# Arduino_MEGA2560_ref.net
KiCad netlist of a schematic drawn in EAGLE
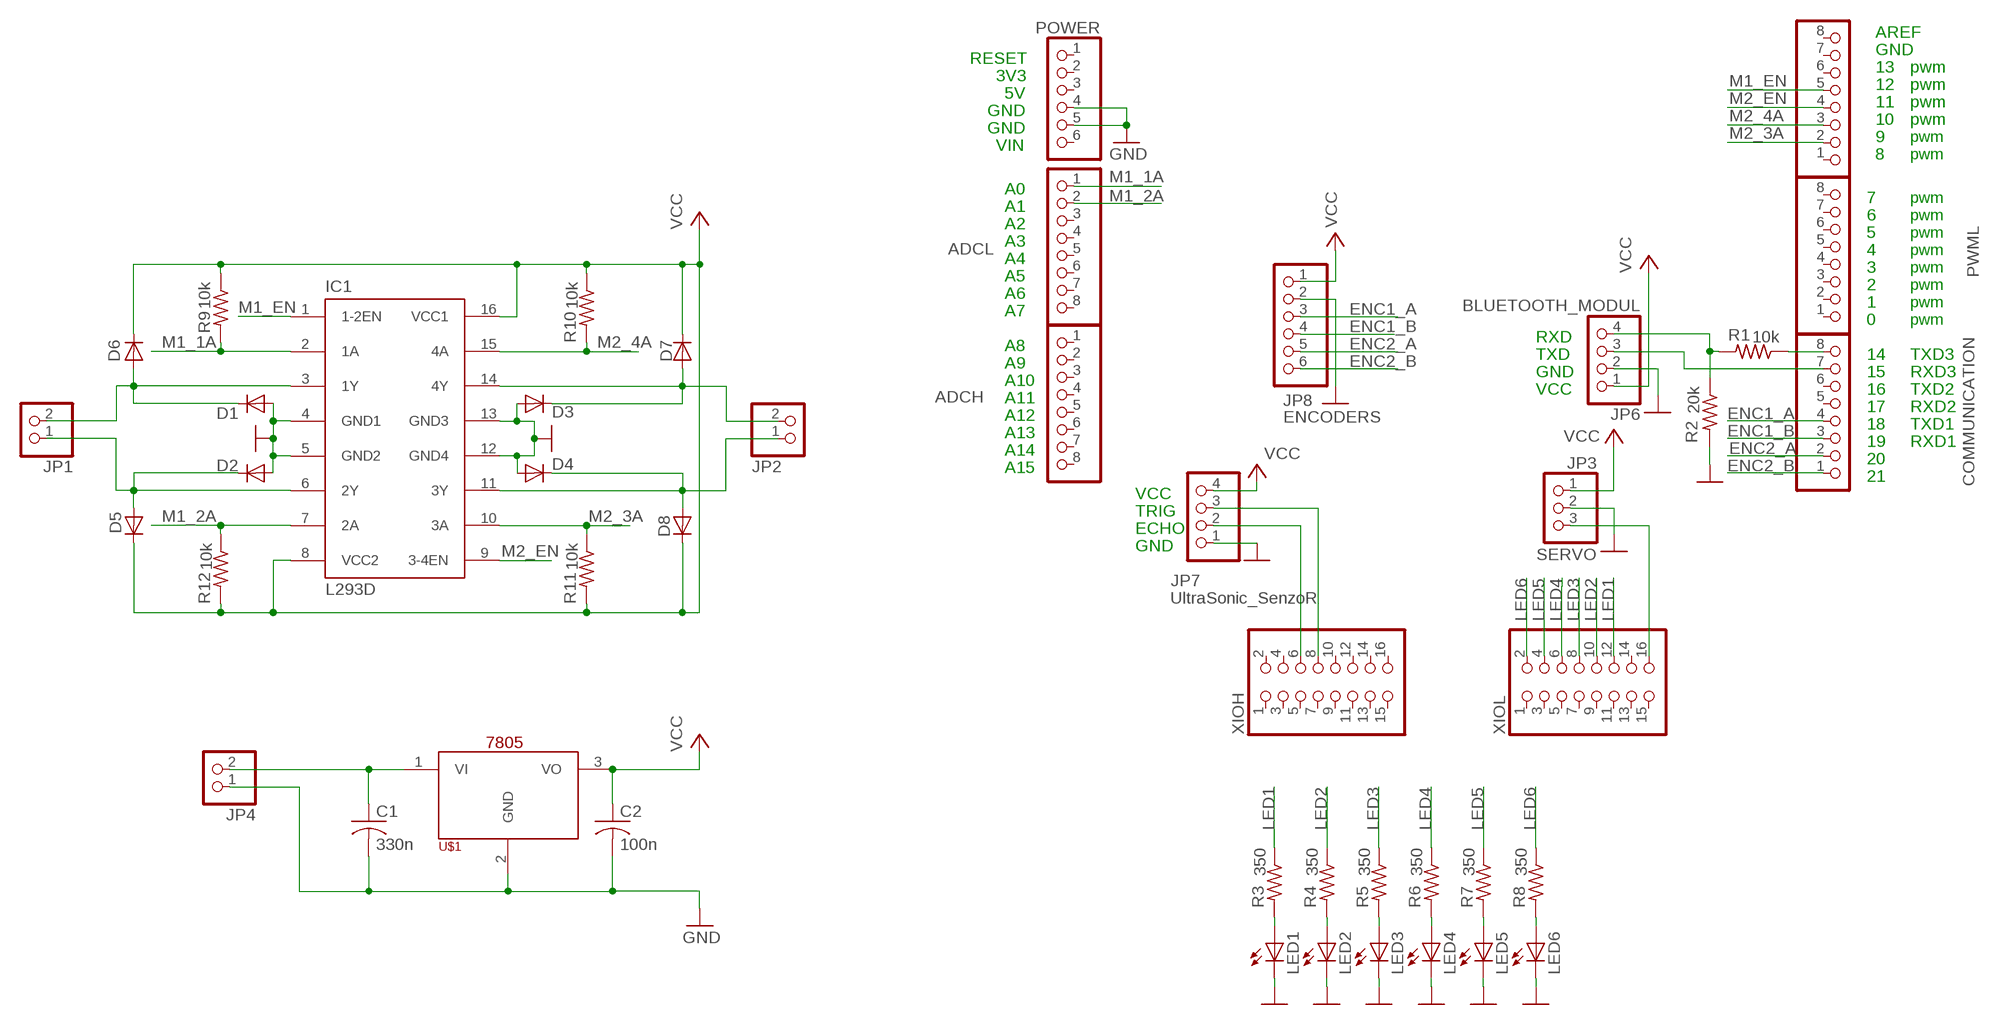
[diagram p0: schematic, sheet 1]

(export (version "E")
  (design (tool "Eeschema 10.0.6"))
  (components
    (comp (ref "ADCH")
      (value "PINHD-1X8")
      (footprint "eagle-import:1X08")
      (libsource (lib "eagle-import") (part "PINHD-1X8"))
    )
    (comp (ref "ADCL")
      (value "PINHD-1X8")
      (footprint "eagle-import:1X08")
      (libsource (lib "eagle-import") (part "PINHD-1X8"))
    )
    (comp (ref "C1")
      (value "330n")
      (footprint "eagle-import:C0805")
      (libsource (lib "eagle-import") (part "C-USC0805"))
    )
    (comp (ref "C2")
      (value "100n")
      (footprint "eagle-import:C0805")
      (libsource (lib "eagle-import") (part "C-USC0805"))
    )
    (comp (ref "COMMUNICATION")
      (value "PINHD-1X8")
      (footprint "eagle-import:1X08")
      (libsource (lib "eagle-import") (part "PINHD-1X8"))
    )
    (comp (ref "D1")
      (value "PMLL4150")
      (footprint "eagle-import:SOD80C")
      (libsource (lib "eagle-import") (part "PMLL4150"))
    )
    (comp (ref "D2")
      (value "PMLL4150")
      (footprint "eagle-import:SOD80C")
      (libsource (lib "eagle-import") (part "PMLL4150"))
    )
    (comp (ref "D3")
      (value "PMLL4150")
      (footprint "eagle-import:SOD80C")
      (libsource (lib "eagle-import") (part "PMLL4150"))
    )
    (comp (ref "D4")
      (value "PMLL4150")
      (footprint "eagle-import:SOD80C")
      (libsource (lib "eagle-import") (part "PMLL4150"))
    )
    (comp (ref "D5")
      (value "PMLL4150")
      (footprint "eagle-import:SOD80C")
      (libsource (lib "eagle-import") (part "PMLL4150"))
    )
    (comp (ref "D6")
      (value "PMLL4150")
      (footprint "eagle-import:SOD80C")
      (libsource (lib "eagle-import") (part "PMLL4150"))
    )
    (comp (ref "D7")
      (value "PMLL4150")
      (footprint "eagle-import:SOD80C")
      (libsource (lib "eagle-import") (part "PMLL4150"))
    )
    (comp (ref "D8")
      (value "PMLL4150")
      (footprint "eagle-import:SOD80C")
      (libsource (lib "eagle-import") (part "PMLL4150"))
    )
    (comp (ref "IC1")
      (value "L293D")
      (footprint "eagle-import:DIL16")
      (libsource (lib "eagle-import") (part "L293D"))
    )
    (comp (ref "JP1")
      (value "PINHD-1X2")
      (footprint "eagle-import:1X02")
      (libsource (lib "eagle-import") (part "PINHD-1X2"))
    )
    (comp (ref "JP2")
      (value "PINHD-1X2")
      (footprint "eagle-import:1X02")
      (libsource (lib "eagle-import") (part "PINHD-1X2"))
    )
    (comp (ref "JP3")
      (value "SERVO")
      (footprint "eagle-import:1X03")
      (libsource (lib "eagle-import") (part "PINHD-1X3"))
    )
    (comp (ref "JP4")
      (value "PINHD-1X2")
      (footprint "eagle-import:1X02")
      (libsource (lib "eagle-import") (part "PINHD-1X2"))
    )
    (comp (ref "JP6")
      (value "BLUETOOTH_MODUL")
      (footprint "eagle-import:1X04")
      (libsource (lib "eagle-import") (part "PINHD-1X4"))
    )
    (comp (ref "JP7")
      (value "UltraSonic_SenzoR")
      (footprint "eagle-import:1X04")
      (libsource (lib "eagle-import") (part "PINHD-1X4"))
    )
    (comp (ref "JP8")
      (value "ENCODERS")
      (footprint "eagle-import:1X06")
      (libsource (lib "eagle-import") (part "PINHD-1X6"))
    )
    (comp (ref "LED1")
      (value "LED")
      (footprint "eagle-import:SMARTLED-TTW")
      (libsource (lib "eagle-import") (part "LED"))
    )
    (comp (ref "LED2")
      (value "LED")
      (footprint "eagle-import:SMARTLED-TTW")
      (libsource (lib "eagle-import") (part "LED"))
    )
    (comp (ref "LED3")
      (value "LED")
      (footprint "eagle-import:SMARTLED-TTW")
      (libsource (lib "eagle-import") (part "LED"))
    )
    (comp (ref "LED4")
      (value "LED")
      (footprint "eagle-import:SMARTLED-TTW")
      (libsource (lib "eagle-import") (part "LED"))
    )
    (comp (ref "LED5")
      (value "LED")
      (footprint "eagle-import:SMARTLED-TTW")
      (libsource (lib "eagle-import") (part "LED"))
    )
    (comp (ref "LED6")
      (value "LED")
      (footprint "eagle-import:SMARTLED-TTW")
      (libsource (lib "eagle-import") (part "LED"))
    )
    (comp (ref "POWER")
      (value "PINHD-1X6")
      (footprint "eagle-import:1X06")
      (libsource (lib "eagle-import") (part "PINHD-1X6"))
    )
    (comp (ref "PWMH")
      (value "PINHD-1X8")
      (footprint "eagle-import:1X08")
      (libsource (lib "eagle-import") (part "PINHD-1X8"))
    )
    (comp (ref "PWML")
      (value "PINHD-1X8")
      (footprint "eagle-import:1X08")
      (libsource (lib "eagle-import") (part "PINHD-1X8"))
    )
    (comp (ref "R1")
      (value "10k")
      (footprint "eagle-import:R0805")
      (libsource (lib "eagle-import") (part "R-US_R0805"))
    )
    (comp (ref "R2")
      (value "20k")
      (footprint "eagle-import:R0805")
      (libsource (lib "eagle-import") (part "R-US_R0805"))
    )
    (comp (ref "R3")
      (value "350")
      (footprint "eagle-import:R0805")
      (libsource (lib "eagle-import") (part "R-US_R0805"))
    )
    (comp (ref "R4")
      (value "350")
      (footprint "eagle-import:R0805")
      (libsource (lib "eagle-import") (part "R-US_R0805"))
    )
    (comp (ref "R5")
      (value "350")
      (footprint "eagle-import:R0805")
      (libsource (lib "eagle-import") (part "R-US_R0805"))
    )
    (comp (ref "R6")
      (value "350")
      (footprint "eagle-import:R0805")
      (libsource (lib "eagle-import") (part "R-US_R0805"))
    )
    (comp (ref "R7")
      (value "350")
      (footprint "eagle-import:R0805")
      (libsource (lib "eagle-import") (part "R-US_R0805"))
    )
    (comp (ref "R8")
      (value "350")
      (footprint "eagle-import:R0805")
      (libsource (lib "eagle-import") (part "R-US_R0805"))
    )
    (comp (ref "R9")
      (value "10k")
      (footprint "eagle-import:R0805")
      (libsource (lib "eagle-import") (part "R-US_R0805"))
    )
    (comp (ref "R10")
      (value "10k")
      (footprint "eagle-import:R0805")
      (libsource (lib "eagle-import") (part "R-US_R0805"))
    )
    (comp (ref "R11")
      (value "10k")
      (footprint "eagle-import:R0805")
      (libsource (lib "eagle-import") (part "R-US_R0805"))
    )
    (comp (ref "R12")
      (value "10k")
      (footprint "eagle-import:R0805")
      (libsource (lib "eagle-import") (part "R-US_R0805"))
    )
    (comp (ref "U$1")
      (value "7805")
      (footprint "eagle-import:TO-220")
      (libsource (lib "eagle-import") (part "7805"))
    )
    (comp (ref "XIOH")
      (value "PINHD-2X8")
      (footprint "eagle-import:2X08")
      (libsource (lib "eagle-import") (part "PINHD-2X8"))
    )
    (comp (ref "XIOL")
      (value "PINHD-2X8")
      (footprint "eagle-import:2X08")
      (libsource (lib "eagle-import") (part "PINHD-2X8"))
    )
  )
  (nets
    (net (code "1") (name "/ENC1_A") (class "Default")
      (node (ref "COMMUNICATION") (pin "4") (pinfunction "4_4") (pintype "passive"))
      (node (ref "JP8") (pin "3") (pinfunction "3_3") (pintype "passive"))
    )
    (net (code "2") (name "/ENC1_B") (class "Default")
      (node (ref "COMMUNICATION") (pin "3") (pinfunction "3_3") (pintype "passive"))
      (node (ref "JP8") (pin "4") (pinfunction "4_4") (pintype "passive"))
    )
    (net (code "3") (name "/ENC2_A") (class "Default")
      (node (ref "COMMUNICATION") (pin "2") (pinfunction "2_2") (pintype "passive"))
      (node (ref "JP8") (pin "5") (pinfunction "5_5") (pintype "passive"))
    )
    (net (code "4") (name "/ENC2_B") (class "Default")
      (node (ref "COMMUNICATION") (pin "1") (pinfunction "1_1") (pintype "passive"))
      (node (ref "JP8") (pin "6") (pinfunction "6_6") (pintype "passive"))
    )
    (net (code "5") (name "/LED1") (class "Default")
      (node (ref "R3") (pin "1") (pinfunction "1_1") (pintype "passive"))
      (node (ref "XIOL") (pin "12") (pinfunction "12_12") (pintype "passive"))
    )
    (net (code "6") (name "/LED2") (class "Default")
      (node (ref "R4") (pin "1") (pinfunction "1_1") (pintype "passive"))
      (node (ref "XIOL") (pin "10") (pinfunction "10_10") (pintype "passive"))
    )
    (net (code "7") (name "/LED3") (class "Default")
      (node (ref "R5") (pin "1") (pinfunction "1_1") (pintype "passive"))
      (node (ref "XIOL") (pin "8") (pinfunction "8_8") (pintype "passive"))
    )
    (net (code "8") (name "/LED4") (class "Default")
      (node (ref "R6") (pin "1") (pinfunction "1_1") (pintype "passive"))
      (node (ref "XIOL") (pin "6") (pinfunction "6_6") (pintype "passive"))
    )
    (net (code "9") (name "/LED5") (class "Default")
      (node (ref "R7") (pin "1") (pinfunction "1_1") (pintype "passive"))
      (node (ref "XIOL") (pin "4") (pinfunction "4_4") (pintype "passive"))
    )
    (net (code "10") (name "/LED6") (class "Default")
      (node (ref "R8") (pin "1") (pinfunction "1_1") (pintype "passive"))
      (node (ref "XIOL") (pin "2") (pinfunction "2_2") (pintype "passive"))
    )
    (net (code "11") (name "/M1_1A") (class "Default")
      (node (ref "ADCL") (pin "1") (pinfunction "1_1") (pintype "passive"))
      (node (ref "IC1") (pin "2") (pinfunction "1A_2") (pintype "input"))
      (node (ref "R9") (pin "2") (pinfunction "2_2") (pintype "passive"))
    )
    (net (code "12") (name "/M1_2A") (class "Default")
      (node (ref "ADCL") (pin "2") (pinfunction "2_2") (pintype "passive"))
      (node (ref "IC1") (pin "7") (pinfunction "2A_7") (pintype "input"))
      (node (ref "R12") (pin "1") (pinfunction "1_1") (pintype "passive"))
    )
    (net (code "13") (name "/M1_EN") (class "Default")
      (node (ref "IC1") (pin "1") (pinfunction "1-2EN_1") (pintype "input"))
      (node (ref "PWMH") (pin "5") (pinfunction "5_5") (pintype "passive"))
    )
    (net (code "14") (name "/M2_3A") (class "Default")
      (node (ref "D4") (pin "C") (pinfunction "C_C") (pintype "passive"))
      (node (ref "D8") (pin "A") (pinfunction "A_A") (pintype "passive"))
      (node (ref "IC1") (pin "11") (pinfunction "3Y_11") (pintype "output"))
      (node (ref "JP2") (pin "1") (pinfunction "1_1") (pintype "passive"))
      (node (ref "PWMH") (pin "2") (pinfunction "2_2") (pintype "passive"))
    )
    (net (code "15") (name "/M2_4A") (class "Default")
      (node (ref "IC1") (pin "15") (pinfunction "4A_15") (pintype "input"))
      (node (ref "PWMH") (pin "3") (pinfunction "3_3") (pintype "passive"))
      (node (ref "R10") (pin "2") (pinfunction "2_2") (pintype "passive"))
    )
    (net (code "16") (name "/M2_EN") (class "Default")
      (node (ref "IC1") (pin "9") (pinfunction "3-4EN_9") (pintype "input"))
      (node (ref "PWMH") (pin "4") (pinfunction "4_4") (pintype "passive"))
    )
    (net (code "17") (name "GND") (class "Default")
      (node (ref "C1") (pin "2") (pinfunction "2_2") (pintype "passive"))
      (node (ref "C2") (pin "2") (pinfunction "2_2") (pintype "passive"))
      (node (ref "D1") (pin "A") (pinfunction "A_A") (pintype "passive"))
      (node (ref "D2") (pin "A") (pinfunction "A_A") (pintype "passive"))
      (node (ref "D3") (pin "A") (pinfunction "A_A") (pintype "passive"))
      (node (ref "D4") (pin "A") (pinfunction "A_A") (pintype "passive"))
      (node (ref "IC1") (pin "12") (pinfunction "GND4_12") (pintype "power_in"))
      (node (ref "IC1") (pin "13") (pinfunction "GND3_13") (pintype "power_in"))
      (node (ref "IC1") (pin "4") (pinfunction "GND1_4") (pintype "power_in"))
      (node (ref "IC1") (pin "5") (pinfunction "GND2_5") (pintype "power_in"))
      (node (ref "JP3") (pin "2") (pinfunction "2_2") (pintype "passive"))
      (node (ref "JP4") (pin "1") (pinfunction "1_1") (pintype "passive"))
      (node (ref "JP6") (pin "2") (pinfunction "2_2") (pintype "passive"))
      (node (ref "JP7") (pin "1") (pinfunction "1_1") (pintype "passive"))
      (node (ref "JP8") (pin "2") (pinfunction "2_2") (pintype "passive"))
      (node (ref "LED1") (pin "C@1") (pinfunction "C_C@1") (pintype "passive"))
      (node (ref "LED2") (pin "C@1") (pinfunction "C_C@1") (pintype "passive"))
      (node (ref "LED3") (pin "C@1") (pinfunction "C_C@1") (pintype "passive"))
      (node (ref "LED4") (pin "C@1") (pinfunction "C_C@1") (pintype "passive"))
      (node (ref "LED5") (pin "C@1") (pinfunction "C_C@1") (pintype "passive"))
      (node (ref "LED6") (pin "C@1") (pinfunction "C_C@1") (pintype "passive"))
      (node (ref "POWER") (pin "4") (pinfunction "4_4") (pintype "passive"))
      (node (ref "POWER") (pin "5") (pinfunction "5_5") (pintype "passive"))
      (node (ref "R2") (pin "2") (pinfunction "2_2") (pintype "passive"))
      (node (ref "U$1") (pin "2") (pinfunction "GND_2") (pintype "bidirectional"))
    )
    (net (code "18") (name "Net-(COMMUNICATION-Pad7)") (class "Default")
      (node (ref "COMMUNICATION") (pin "7") (pinfunction "7_7") (pintype "passive"))
      (node (ref "JP6") (pin "3") (pinfunction "3_3") (pintype "passive"))
    )
    (net (code "19") (name "Net-(COMMUNICATION-Pad8)") (class "Default")
      (node (ref "COMMUNICATION") (pin "8") (pinfunction "8_8") (pintype "passive"))
      (node (ref "R1") (pin "1") (pinfunction "1_1") (pintype "passive"))
    )
    (net (code "20") (name "Net-(IC1-1Y)") (class "Default")
      (node (ref "D1") (pin "C") (pinfunction "C_C") (pintype "passive"))
      (node (ref "D6") (pin "A") (pinfunction "A_A") (pintype "passive"))
      (node (ref "IC1") (pin "3") (pinfunction "1Y_3") (pintype "output"))
      (node (ref "JP1") (pin "2") (pinfunction "2_2") (pintype "passive"))
    )
    (net (code "21") (name "Net-(IC1-2Y)") (class "Default")
      (node (ref "D2") (pin "C") (pinfunction "C_C") (pintype "passive"))
      (node (ref "D5") (pin "A") (pinfunction "A_A") (pintype "passive"))
      (node (ref "IC1") (pin "6") (pinfunction "2Y_6") (pintype "output"))
      (node (ref "JP1") (pin "1") (pinfunction "1_1") (pintype "passive"))
    )
    (net (code "22") (name "Net-(IC1-3A)") (class "Default")
      (node (ref "IC1") (pin "10") (pinfunction "3A_10") (pintype "input"))
      (node (ref "R11") (pin "1") (pinfunction "1_1") (pintype "passive"))
    )
    (net (code "23") (name "Net-(IC1-4Y)") (class "Default")
      (node (ref "D3") (pin "C") (pinfunction "C_C") (pintype "passive"))
      (node (ref "D7") (pin "A") (pinfunction "A_A") (pintype "passive"))
      (node (ref "IC1") (pin "14") (pinfunction "4Y_14") (pintype "output"))
      (node (ref "JP2") (pin "2") (pinfunction "2_2") (pintype "passive"))
    )
    (net (code "24") (name "Net-(JP3-Pad3)") (class "Default")
      (node (ref "JP3") (pin "3") (pinfunction "3_3") (pintype "passive"))
      (node (ref "XIOL") (pin "16") (pinfunction "16_16") (pintype "passive"))
    )
    (net (code "25") (name "Net-(JP6-Pad4)") (class "Default")
      (node (ref "JP6") (pin "4") (pinfunction "4_4") (pintype "passive"))
      (node (ref "R1") (pin "2") (pinfunction "2_2") (pintype "passive"))
      (node (ref "R2") (pin "1") (pinfunction "1_1") (pintype "passive"))
    )
    (net (code "26") (name "Net-(JP7-Pad2)") (class "Default")
      (node (ref "JP7") (pin "2") (pinfunction "2_2") (pintype "passive"))
      (node (ref "XIOH") (pin "6") (pinfunction "6_6") (pintype "passive"))
    )
    (net (code "27") (name "Net-(JP7-Pad3)") (class "Default")
      (node (ref "JP7") (pin "3") (pinfunction "3_3") (pintype "passive"))
      (node (ref "XIOH") (pin "8") (pinfunction "8_8") (pintype "passive"))
    )
    (net (code "28") (name "Net-(LED1-A)") (class "Default")
      (node (ref "LED1") (pin "A@1") (pinfunction "A_A@1") (pintype "passive"))
      (node (ref "R3") (pin "2") (pinfunction "2_2") (pintype "passive"))
    )
    (net (code "29") (name "Net-(LED2-A)") (class "Default")
      (node (ref "LED2") (pin "A@1") (pinfunction "A_A@1") (pintype "passive"))
      (node (ref "R4") (pin "2") (pinfunction "2_2") (pintype "passive"))
    )
    (net (code "30") (name "Net-(LED3-A)") (class "Default")
      (node (ref "LED3") (pin "A@1") (pinfunction "A_A@1") (pintype "passive"))
      (node (ref "R5") (pin "2") (pinfunction "2_2") (pintype "passive"))
    )
    (net (code "31") (name "Net-(LED4-A)") (class "Default")
      (node (ref "LED4") (pin "A@1") (pinfunction "A_A@1") (pintype "passive"))
      (node (ref "R6") (pin "2") (pinfunction "2_2") (pintype "passive"))
    )
    (net (code "32") (name "Net-(LED5-A)") (class "Default")
      (node (ref "LED5") (pin "A@1") (pinfunction "A_A@1") (pintype "passive"))
      (node (ref "R7") (pin "2") (pinfunction "2_2") (pintype "passive"))
    )
    (net (code "33") (name "Net-(LED6-A)") (class "Default")
      (node (ref "LED6") (pin "A@1") (pinfunction "A_A@1") (pintype "passive"))
      (node (ref "R8") (pin "2") (pinfunction "2_2") (pintype "passive"))
    )
    (net (code "34") (name "Net-(U$1-VI)") (class "Default")
      (node (ref "C1") (pin "1") (pinfunction "1_1") (pintype "passive"))
      (node (ref "JP4") (pin "2") (pinfunction "2_2") (pintype "passive"))
      (node (ref "U$1") (pin "1") (pinfunction "VI_1") (pintype "bidirectional"))
    )
    (net (code "35") (name "VCC") (class "Default")
      (node (ref "C2") (pin "1") (pinfunction "1_1") (pintype "passive"))
      (node (ref "D5") (pin "C") (pinfunction "C_C") (pintype "passive"))
      (node (ref "D6") (pin "C") (pinfunction "C_C") (pintype "passive"))
      (node (ref "D7") (pin "C") (pinfunction "C_C") (pintype "passive"))
      (node (ref "D8") (pin "C") (pinfunction "C_C") (pintype "passive"))
      (node (ref "IC1") (pin "16") (pinfunction "VCC1_16") (pintype "power_in"))
      (node (ref "IC1") (pin "8") (pinfunction "VCC2_8") (pintype "power_in"))
      (node (ref "JP3") (pin "1") (pinfunction "1_1") (pintype "passive"))
      (node (ref "JP6") (pin "1") (pinfunction "1_1") (pintype "passive"))
      (node (ref "JP7") (pin "4") (pinfunction "4_4") (pintype "passive"))
      (node (ref "JP8") (pin "1") (pinfunction "1_1") (pintype "passive"))
      (node (ref "R10") (pin "1") (pinfunction "1_1") (pintype "passive"))
      (node (ref "R11") (pin "2") (pinfunction "2_2") (pintype "passive"))
      (node (ref "R12") (pin "2") (pinfunction "2_2") (pintype "passive"))
      (node (ref "R9") (pin "1") (pinfunction "1_1") (pintype "passive"))
      (node (ref "U$1") (pin "3") (pinfunction "VO_3") (pintype "bidirectional"))
    )
    (net (code "36") (name "unconnected-(ADCH-Pad1)") (class "Default")
      (node (ref "ADCH") (pin "1") (pinfunction "1_1") (pintype "passive"))
    )
    (net (code "37") (name "unconnected-(ADCH-Pad2)") (class "Default")
      (node (ref "ADCH") (pin "2") (pinfunction "2_2") (pintype "passive"))
    )
    (net (code "38") (name "unconnected-(ADCH-Pad3)") (class "Default")
      (node (ref "ADCH") (pin "3") (pinfunction "3_3") (pintype "passive"))
    )
    (net (code "39") (name "unconnected-(ADCH-Pad4)") (class "Default")
      (node (ref "ADCH") (pin "4") (pinfunction "4_4") (pintype "passive"))
    )
    (net (code "40") (name "unconnected-(ADCH-Pad5)") (class "Default")
      (node (ref "ADCH") (pin "5") (pinfunction "5_5") (pintype "passive"))
    )
    (net (code "41") (name "unconnected-(ADCH-Pad6)") (class "Default")
      (node (ref "ADCH") (pin "6") (pinfunction "6_6") (pintype "passive"))
    )
    (net (code "42") (name "unconnected-(ADCH-Pad7)") (class "Default")
      (node (ref "ADCH") (pin "7") (pinfunction "7_7") (pintype "passive"))
    )
    (net (code "43") (name "unconnected-(ADCH-Pad8)") (class "Default")
      (node (ref "ADCH") (pin "8") (pinfunction "8_8") (pintype "passive"))
    )
    (net (code "44") (name "unconnected-(ADCL-Pad3)") (class "Default")
      (node (ref "ADCL") (pin "3") (pinfunction "3_3") (pintype "passive"))
    )
    (net (code "45") (name "unconnected-(ADCL-Pad4)") (class "Default")
      (node (ref "ADCL") (pin "4") (pinfunction "4_4") (pintype "passive"))
    )
    (net (code "46") (name "unconnected-(ADCL-Pad5)") (class "Default")
      (node (ref "ADCL") (pin "5") (pinfunction "5_5") (pintype "passive"))
    )
    (net (code "47") (name "unconnected-(ADCL-Pad6)") (class "Default")
      (node (ref "ADCL") (pin "6") (pinfunction "6_6") (pintype "passive"))
    )
    (net (code "48") (name "unconnected-(ADCL-Pad7)") (class "Default")
      (node (ref "ADCL") (pin "7") (pinfunction "7_7") (pintype "passive"))
    )
    (net (code "49") (name "unconnected-(ADCL-Pad8)") (class "Default")
      (node (ref "ADCL") (pin "8") (pinfunction "8_8") (pintype "passive"))
    )
    (net (code "50") (name "unconnected-(COMMUNICATION-Pad5)") (class "Default")
      (node (ref "COMMUNICATION") (pin "5") (pinfunction "5_5") (pintype "passive"))
    )
    (net (code "51") (name "unconnected-(COMMUNICATION-Pad6)") (class "Default")
      (node (ref "COMMUNICATION") (pin "6") (pinfunction "6_6") (pintype "passive"))
    )
    (net (code "52") (name "unconnected-(POWER-Pad1)") (class "Default")
      (node (ref "POWER") (pin "1") (pinfunction "1_1") (pintype "passive"))
    )
    (net (code "53") (name "unconnected-(POWER-Pad2)") (class "Default")
      (node (ref "POWER") (pin "2") (pinfunction "2_2") (pintype "passive"))
    )
    (net (code "54") (name "unconnected-(POWER-Pad3)") (class "Default")
      (node (ref "POWER") (pin "3") (pinfunction "3_3") (pintype "passive"))
    )
    (net (code "55") (name "unconnected-(POWER-Pad6)") (class "Default")
      (node (ref "POWER") (pin "6") (pinfunction "6_6") (pintype "passive"))
    )
    (net (code "56") (name "unconnected-(PWMH-Pad1)") (class "Default")
      (node (ref "PWMH") (pin "1") (pinfunction "1_1") (pintype "passive"))
    )
    (net (code "57") (name "unconnected-(PWMH-Pad6)") (class "Default")
      (node (ref "PWMH") (pin "6") (pinfunction "6_6") (pintype "passive"))
    )
    (net (code "58") (name "unconnected-(PWMH-Pad7)") (class "Default")
      (node (ref "PWMH") (pin "7") (pinfunction "7_7") (pintype "passive"))
    )
    (net (code "59") (name "unconnected-(PWMH-Pad8)") (class "Default")
      (node (ref "PWMH") (pin "8") (pinfunction "8_8") (pintype "passive"))
    )
    (net (code "60") (name "unconnected-(PWML-Pad1)") (class "Default")
      (node (ref "PWML") (pin "1") (pinfunction "1_1") (pintype "passive"))
    )
    (net (code "61") (name "unconnected-(PWML-Pad2)") (class "Default")
      (node (ref "PWML") (pin "2") (pinfunction "2_2") (pintype "passive"))
    )
    (net (code "62") (name "unconnected-(PWML-Pad3)") (class "Default")
      (node (ref "PWML") (pin "3") (pinfunction "3_3") (pintype "passive"))
    )
    (net (code "63") (name "unconnected-(PWML-Pad4)") (class "Default")
      (node (ref "PWML") (pin "4") (pinfunction "4_4") (pintype "passive"))
    )
    (net (code "64") (name "unconnected-(PWML-Pad5)") (class "Default")
      (node (ref "PWML") (pin "5") (pinfunction "5_5") (pintype "passive"))
    )
    (net (code "65") (name "unconnected-(PWML-Pad6)") (class "Default")
      (node (ref "PWML") (pin "6") (pinfunction "6_6") (pintype "passive"))
    )
    (net (code "66") (name "unconnected-(PWML-Pad7)") (class "Default")
      (node (ref "PWML") (pin "7") (pinfunction "7_7") (pintype "passive"))
    )
    (net (code "67") (name "unconnected-(PWML-Pad8)") (class "Default")
      (node (ref "PWML") (pin "8") (pinfunction "8_8") (pintype "passive"))
    )
    (net (code "68") (name "unconnected-(XIOH-Pad1)") (class "Default")
      (node (ref "XIOH") (pin "1") (pinfunction "1_1") (pintype "passive"))
    )
    (net (code "69") (name "unconnected-(XIOH-Pad2)") (class "Default")
      (node (ref "XIOH") (pin "2") (pinfunction "2_2") (pintype "passive"))
    )
    (net (code "70") (name "unconnected-(XIOH-Pad3)") (class "Default")
      (node (ref "XIOH") (pin "3") (pinfunction "3_3") (pintype "passive"))
    )
    (net (code "71") (name "unconnected-(XIOH-Pad4)") (class "Default")
      (node (ref "XIOH") (pin "4") (pinfunction "4_4") (pintype "passive"))
    )
    (net (code "72") (name "unconnected-(XIOH-Pad5)") (class "Default")
      (node (ref "XIOH") (pin "5") (pinfunction "5_5") (pintype "passive"))
    )
    (net (code "73") (name "unconnected-(XIOH-Pad7)") (class "Default")
      (node (ref "XIOH") (pin "7") (pinfunction "7_7") (pintype "passive"))
    )
    (net (code "74") (name "unconnected-(XIOH-Pad9)") (class "Default")
      (node (ref "XIOH") (pin "9") (pinfunction "9_9") (pintype "passive"))
    )
    (net (code "75") (name "unconnected-(XIOH-Pad10)") (class "Default")
      (node (ref "XIOH") (pin "10") (pinfunction "10_10") (pintype "passive"))
    )
    (net (code "76") (name "unconnected-(XIOH-Pad11)") (class "Default")
      (node (ref "XIOH") (pin "11") (pinfunction "11_11") (pintype "passive"))
    )
    (net (code "77") (name "unconnected-(XIOH-Pad12)") (class "Default")
      (node (ref "XIOH") (pin "12") (pinfunction "12_12") (pintype "passive"))
    )
    (net (code "78") (name "unconnected-(XIOH-Pad13)") (class "Default")
      (node (ref "XIOH") (pin "13") (pinfunction "13_13") (pintype "passive"))
    )
    (net (code "79") (name "unconnected-(XIOH-Pad14)") (class "Default")
      (node (ref "XIOH") (pin "14") (pinfunction "14_14") (pintype "passive"))
    )
    (net (code "80") (name "unconnected-(XIOH-Pad15)") (class "Default")
      (node (ref "XIOH") (pin "15") (pinfunction "15_15") (pintype "passive"))
    )
    (net (code "81") (name "unconnected-(XIOH-Pad16)") (class "Default")
      (node (ref "XIOH") (pin "16") (pinfunction "16_16") (pintype "passive"))
    )
    (net (code "82") (name "unconnected-(XIOL-Pad1)") (class "Default")
      (node (ref "XIOL") (pin "1") (pinfunction "1_1") (pintype "passive"))
    )
    (net (code "83") (name "unconnected-(XIOL-Pad3)") (class "Default")
      (node (ref "XIOL") (pin "3") (pinfunction "3_3") (pintype "passive"))
    )
    (net (code "84") (name "unconnected-(XIOL-Pad5)") (class "Default")
      (node (ref "XIOL") (pin "5") (pinfunction "5_5") (pintype "passive"))
    )
    (net (code "85") (name "unconnected-(XIOL-Pad7)") (class "Default")
      (node (ref "XIOL") (pin "7") (pinfunction "7_7") (pintype "passive"))
    )
    (net (code "86") (name "unconnected-(XIOL-Pad9)") (class "Default")
      (node (ref "XIOL") (pin "9") (pinfunction "9_9") (pintype "passive"))
    )
    (net (code "87") (name "unconnected-(XIOL-Pad11)") (class "Default")
      (node (ref "XIOL") (pin "11") (pinfunction "11_11") (pintype "passive"))
    )
    (net (code "88") (name "unconnected-(XIOL-Pad13)") (class "Default")
      (node (ref "XIOL") (pin "13") (pinfunction "13_13") (pintype "passive"))
    )
    (net (code "89") (name "unconnected-(XIOL-Pad14)") (class "Default")
      (node (ref "XIOL") (pin "14") (pinfunction "14_14") (pintype "passive"))
    )
    (net (code "90") (name "unconnected-(XIOL-Pad15)") (class "Default")
      (node (ref "XIOL") (pin "15") (pinfunction "15_15") (pintype "passive"))
    )
  )
)
